# ControlBoard_p2.net
KiCad netlist of a schematic drawn in Altium Designer
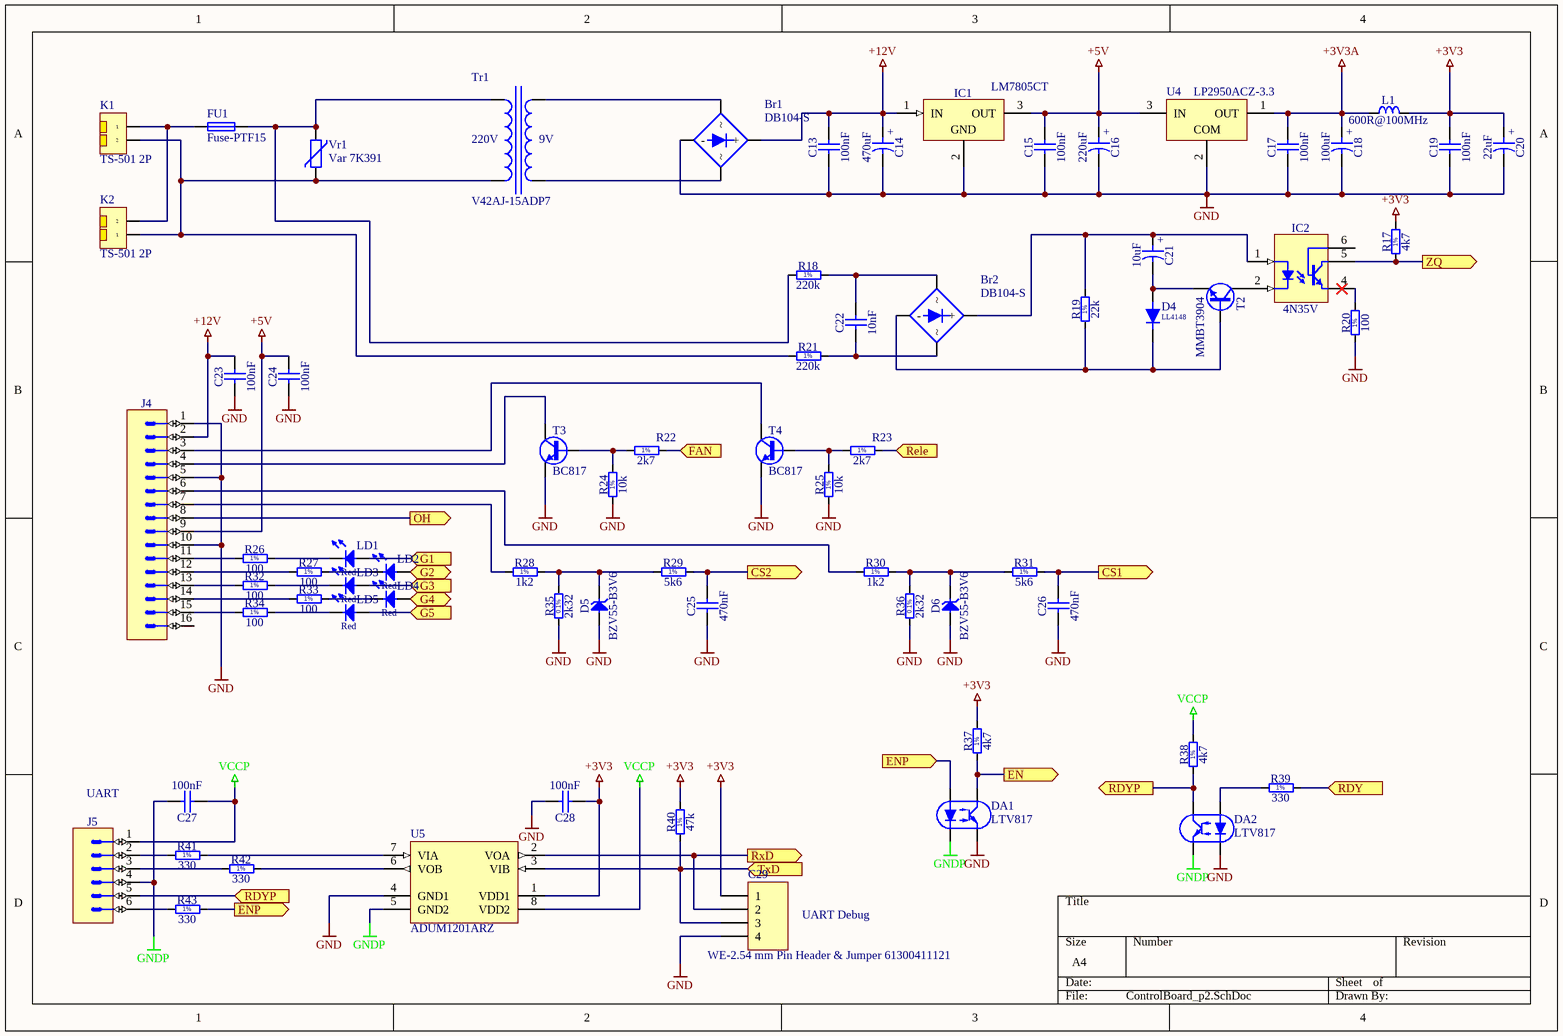
[diagram p0: ControlBoard_p2.SchDoc]

(export (version "E")
  (design (tool "Eeschema 10.0.6"))
  (components
    (comp (ref "Br1")
      (value "DB104-S")
      (footprint "DB-S")
      (description "SMD 1A 400V")
      (libsource (lib "Diodes-Bridge") (part "DB104-S"))
    )
    (comp (ref "Br2")
      (value "DB104-S")
      (footprint "DB-S")
      (description "SMD 1A 400V")
      (libsource (lib "Diodes-Bridge") (part "DB104-S"))
    )
    (comp (ref "C13")
      (value "100nF")
      (footprint "CAPC2012X135N")
      (description "Non-polarised capacitor")
      (fields
        (field (name "PART NUMBER") "CC0805_100NF_50V_10%_X7R")
        (field (name "VOLTAGE") "50V")
        (field (name "AUTHOR") "CERN DEM JLC")
      )
      (libsource (lib "Capacitors") (part "Capacitor - non polarized"))
    )
    (comp (ref "C14")
      (value "470uF")
      (footprint "CAPPR500-1050X2200")
      (description "Polarised capacitor")
      (fields
        (field (name "PART NUMBER") "CAER_470UF_25V_20%_500-1050X2200_LESR0R062")
        (field (name "VOLTAGE") "25V")
        (field (name "AUTHOR") "CERN DEM JLC")
      )
      (libsource (lib "Capacitors") (part "Capacitor - polarized"))
    )
    (comp (ref "C15")
      (value "100nF")
      (footprint "CAPC2012X135N")
      (description "Non-polarised capacitor")
      (fields
        (field (name "PART NUMBER") "CC0805_100NF_50V_10%_X7R")
        (field (name "VOLTAGE") "50V")
        (field (name "AUTHOR") "CERN DEM JLC")
      )
      (libsource (lib "Capacitors") (part "Capacitor - non polarized"))
    )
    (comp (ref "C16")
      (value "220uF")
      (footprint "CAPPR350-850X1300")
      (description "Polarised capacitor")
      (fields
        (field (name "PART NUMBER") "CAER_220UF_25V_20%_RUBYCON_25YXF220M8X11.5")
        (field (name "VOLTAGE") "25V")
        (field (name "AUTHOR") "CERN DEM JLC")
      )
      (libsource (lib "Capacitors") (part "Capacitor - polarized"))
    )
    (comp (ref "C17")
      (value "100nF")
      (footprint "CAPC2012X135N")
      (description "Non-polarised capacitor")
      (fields
        (field (name "PART NUMBER") "CC0805_100NF_50V_10%_X7R")
        (field (name "VOLTAGE") "50V")
        (field (name "AUTHOR") "CERN DEM JLC")
      )
      (libsource (lib "Capacitors") (part "Capacitor - non polarized"))
    )
    (comp (ref "C18")
      (value "100uF")
      (footprint "CAPPR350-850X800")
      (description "Polarised capacitor")
      (fields
        (field (name "PART NUMBER") "CAER_100UF_25V_20%_RUBYCON_25ML100M8X7")
        (field (name "VOLTAGE") "25V")
        (field (name "AUTHOR") "CERN DEM JMW")
      )
      (libsource (lib "Capacitors") (part "Capacitor - polarized"))
    )
    (comp (ref "C19")
      (value "100nF")
      (footprint "CAPC2012X135N")
      (description "Non-polarised capacitor")
      (fields
        (field (name "PART NUMBER") "CC0805_100NF_50V_10%_X7R")
        (field (name "VOLTAGE") "50V")
        (field (name "AUTHOR") "CERN DEM JLC")
      )
      (libsource (lib "Capacitors") (part "Capacitor - non polarized"))
    )
    (comp (ref "C20")
      (value "22uF")
      (footprint "CAPPRB254-600X990")
      (description "Polarised capacitor")
      (fields
        (field (name "PART NUMBER") "CTEB_22UF_16V_10%_254-600X990")
        (field (name "VOLTAGE") "16V")
        (field (name "AUTHOR") "CERN DEM JLC")
      )
      (libsource (lib "Capacitors") (part "Capacitor - polarized"))
    )
    (comp (ref "C21")
      (value "10uF")
      (footprint "CAPPR200-500X1100")
      (description "Polarised capacitor")
      (fields
        (field (name "PART NUMBER") "CAER_10UF_63V_20%_PANASONIC_ECA1JM100")
        (field (name "VOLTAGE") "63V")
        (field (name "AUTHOR") "CERN DEM JLC")
      )
      (libsource (lib "Capacitors") (part "Capacitor - polarized"))
    )
    (comp (ref "C22")
      (value "10nF")
      (footprint "CAPR500-300X720X650")
      (description "Non-polarised capacitor")
      (fields
        (field (name "PART NUMBER") "CPER_10NF_400V_10%_500-300X720X650")
        (field (name "VOLTAGE") "400VDC/200VAC")
        (field (name "AUTHOR") "CERN DEM JLC")
      )
      (libsource (lib "Capacitors") (part "Capacitor - non polarized"))
    )
    (comp (ref "C23")
      (value "100nF")
      (footprint "CAPC2012X135N")
      (description "Non-polarised capacitor")
      (fields
        (field (name "PART NUMBER") "CC0805_100NF_50V_10%_X7R")
        (field (name "VOLTAGE") "50V")
        (field (name "AUTHOR") "CERN DEM JLC")
      )
      (libsource (lib "Capacitors") (part "Capacitor - non polarized"))
    )
    (comp (ref "C24")
      (value "100nF")
      (footprint "CAPC2012X135N")
      (description "Non-polarised capacitor")
      (fields
        (field (name "PART NUMBER") "CC0805_100NF_50V_10%_X7R")
        (field (name "VOLTAGE") "50V")
        (field (name "AUTHOR") "CERN DEM JLC")
      )
      (libsource (lib "Capacitors") (part "Capacitor - non polarized"))
    )
    (comp (ref "C25")
      (value "470nF")
      (footprint "CAPC2012X110N")
      (description "Non-polarised capacitor")
      (fields
        (field (name "PART NUMBER") "CC0805_470NF_50V_10%_X7R")
        (field (name "VOLTAGE") "50V")
        (field (name "AUTHOR") "CERN DEM JLC")
      )
      (libsource (lib "Capacitors") (part "Capacitor - non polarized"))
    )
    (comp (ref "C26")
      (value "470nF")
      (footprint "CAPC2012X110N")
      (description "Non-polarised capacitor")
      (fields
        (field (name "PART NUMBER") "CC0805_470NF_50V_10%_X7R")
        (field (name "VOLTAGE") "50V")
        (field (name "AUTHOR") "CERN DEM JLC")
      )
      (libsource (lib "Capacitors") (part "Capacitor - non polarized"))
    )
    (comp (ref "C27")
      (value "100nF")
      (footprint "CAPC2012X135N")
      (description "Non-polarised capacitor")
      (fields
        (field (name "PART NUMBER") "CC0805_100NF_50V_10%_X7R")
        (field (name "VOLTAGE") "50V")
        (field (name "AUTHOR") "CERN DEM JLC")
      )
      (libsource (lib "Capacitors") (part "Capacitor - non polarized"))
    )
    (comp (ref "C28")
      (value "100nF")
      (footprint "CAPC2012X135N")
      (description "Non-polarised capacitor")
      (fields
        (field (name "PART NUMBER") "CC0805_100NF_50V_10%_X7R")
        (field (name "VOLTAGE") "50V")
        (field (name "AUTHOR") "CERN DEM JLC")
      )
      (libsource (lib "Capacitors") (part "Capacitor - non polarized"))
    )
    (comp (ref "C29")
      (value "WE-2.54 mm Pin Header & Jumper 61300411121")
      (footprint "61300411121")
      (description "WR-PHD 2.54mm Pin Header")
      (fields
        (field (name "MANUFACTURER") "WЁ№rth Elektronik eiSos GmbH")
        (field (name "PARTNO") "61300411121")
        (field (name "CREATED BY") "Karrer Zheng")
      )
      (libsource (lib "WE_WR-PHD_Pin Header_2.54mm_rev15c") (part "WE-2.54 mm Pin Header & Jumper 61300411121"))
    )
    (comp (ref "D4")
      (value "LL4148")
      (footprint "SOD80/MLL34")
      (description "75V 0.3A SOD80/MLL34")
      (libsource (lib "Diodes") (part "LL4148"))
    )
    (comp (ref "D5")
      (value "BZV55-B3V6")
      (footprint "DIOMELF3515N")
      (description "Zener Diode")
      (fields
        (field (name "VOLTAGE") "3V6")
        (field (name "POWER") "500mW")
        (field (name "AUTHOR") "CERN DEM JLC")
      )
      (libsource (lib "ICs And Semiconductors") (part "Diode Zener"))
    )
    (comp (ref "D6")
      (value "BZV55-B3V6")
      (footprint "DIOMELF3515N")
      (description "Zener Diode")
      (fields
        (field (name "VOLTAGE") "3V6")
        (field (name "POWER") "500mW")
        (field (name "AUTHOR") "CERN DEM JLC")
      )
      (libsource (lib "ICs And Semiconductors") (part "Diode Zener"))
    )
    (comp (ref "DA1")
      (value "LTV817")
      (footprint "DIL4-300a")
      (libsource (lib "Opto Coupler") (part "LTV817"))
    )
    (comp (ref "DA2") (value "LTV817") (footprint "DIL4-300a") (libsource (lib "") (part "LTV817_1")))
    (comp (ref "FU1")
      (value "Fuse-PTF15")
      (footprint "FUSE-MCH")
      (description "5mm 6.3A")
      (libsource (lib "Devise") (part "Fuse-PTF15"))
    )
    (comp (ref "IC1")
      (value "LM7805CT")
      (footprint "TO-220-V")
      (description "3-Terminal Regulator 1=IN 2=GND 3=OUT")
      (fields
        (field (name "PART NUMBER") "LM7805CT_v")
        (field (name "MANUFACTURER") "FAIRCHILD SEMICONDUCTOR")
        (field (name "AUTHOR") "CERN DEM JLC")
      )
      (libsource (lib "ICs And Semiconductors") (part "REG3 1IN-2GND-3OUT"))
    )
    (comp (ref "IC2")
      (value "4N35V")
      (footprint "DIP6-300")
      (description "Single Optocoupler with Base")
      (fields
        (field (name "MANUFACTURER") "VISHAY SEMICONDUCTORS")
        (field (name "MANUFACTURER PART NUMBER") "4N25V")
        (field (name "AUTHOR") "CERN DEM JLC")
      )
      (libsource (lib "ICs And Semiconductors") (part "Optocoupler Type4"))
    )
    (comp (ref "J4")
      (value "Header 16")
      (footprint "3M_N2516-6002RB")
      (description "Connector 16 Male")
      (fields
        (field (name "PART NUMBER") "3M_N2516-6002RB")
        (field (name "MANUFACTURER") "3M")
        (field (name "AUTHOR") "CERN DEM JLC")
      )
      (libsource (lib "Connectors") (part "Connector 16 Male"))
    )
    (comp (ref "J5")
      (value "KK®")
      (footprint "MOLEX_22-27-2061")
      (description "Connector 6 Male")
      (fields
        (field (name "PART NUMBER") "MOLEX_22-27-2061")
        (field (name "MANUFACTURER") "MOLEX")
        (field (name "AUTHOR") "CERN DEM JMW")
      )
      (libsource (lib "Connectors") (part "Connector 6 Male"))
    )
    (comp (ref "K1")
      (value "TS-501 2P")
      (footprint "TS-501 2P-2.5")
      (description "10A/300V AC 5mm")
      (libsource (lib "Connektor") (part "TS-501 2P"))
    )
    (comp (ref "K2")
      (value "TS-501 2P")
      (footprint "TS-501 2P-2.5")
      (description "10A/300V AC 5mm")
      (libsource (lib "") (part "TS-501 2P_1"))
    )
    (comp (ref "L1")
      (value "600R@100MHz")
      (footprint "INDC2012X110N")
      (description "Inductor")
      (fields
        (field (name "PART NUMBER") "IND0805_WURTH_742792040")
        (field (name "POWER") "2A")
        (field (name "AUTHOR") "CERN DEM JLC")
      )
      (libsource (lib "Inductors & Transformers") (part "Inductor"))
    )
    (comp (ref "LD1")
      (value "Super Red")
      (footprint "LED_OSRAM_LSR976")
      (description "LED Red 1C 2A")
      (fields
        (field (name "PART NUMBER") "LED_OSRAM_LSR976")
        (field (name "MANUFACTURER") "OSRAM")
        (field (name "AUTHOR") "CERN DEM JLC")
      )
      (libsource (lib "ICs And Semiconductors") (part "LED Red 1C 2A"))
    )
    (comp (ref "LD2")
      (value "Super Red")
      (footprint "LED_OSRAM_LSR976")
      (description "LED Red 1C 2A")
      (fields
        (field (name "PART NUMBER") "LED_OSRAM_LSR976")
        (field (name "MANUFACTURER") "OSRAM")
        (field (name "AUTHOR") "CERN DEM JLC")
      )
      (libsource (lib "ICs And Semiconductors") (part "LED Red 1C 2A"))
    )
    (comp (ref "LD3")
      (value "Super Red")
      (footprint "LED_OSRAM_LSR976")
      (description "LED Red 1C 2A")
      (fields
        (field (name "PART NUMBER") "LED_OSRAM_LSR976")
        (field (name "MANUFACTURER") "OSRAM")
        (field (name "AUTHOR") "CERN DEM JLC")
      )
      (libsource (lib "ICs And Semiconductors") (part "LED Red 1C 2A"))
    )
    (comp (ref "LD4")
      (value "Super Red")
      (footprint "LED_OSRAM_LSR976")
      (description "LED Red 1C 2A")
      (fields
        (field (name "PART NUMBER") "LED_OSRAM_LSR976")
        (field (name "MANUFACTURER") "OSRAM")
        (field (name "AUTHOR") "CERN DEM JLC")
      )
      (libsource (lib "ICs And Semiconductors") (part "LED Red 1C 2A"))
    )
    (comp (ref "LD5")
      (value "Super Red")
      (footprint "LED_OSRAM_LSR976")
      (description "LED Red 1C 2A")
      (fields
        (field (name "PART NUMBER") "LED_OSRAM_LSR976")
        (field (name "MANUFACTURER") "OSRAM")
        (field (name "AUTHOR") "CERN DEM JLC")
      )
      (libsource (lib "ICs And Semiconductors") (part "LED Red 1C 2A"))
    )
    (comp (ref "R17")
      (value "4k7")
      (footprint "RESC2012X60N")
      (description "Resistor - 1%")
      (fields
        (field (name "PART NUMBER") "R0805_4K7_1%_0.125W_100PPM")
        (field (name "POWER") "0.125W")
        (field (name "AUTHOR") "CERN DEM JLC")
      )
      (libsource (lib "Resistors") (part "Resistor - 1%"))
    )
    (comp (ref "R18")
      (value "220k")
      (footprint "RES1016-630X250")
      (description "Resistor - 1%")
      (fields
        (field (name "PART NUMBER") "RMF_220K_1%_0.6W_50PPM_1016-630X250")
        (field (name "POWER") "0.6W")
        (field (name "AUTHOR") "CERN DEM JLC")
      )
      (libsource (lib "Resistors") (part "Resistor - 1%"))
    )
    (comp (ref "R19")
      (value "22k")
      (footprint "RESC2012X60N")
      (description "Resistor - 1%")
      (fields
        (field (name "PART NUMBER") "R0805_22K_1%_0.125W_100PPM")
        (field (name "POWER") "0.125W")
        (field (name "AUTHOR") "CERN DEM JLC")
      )
      (libsource (lib "Resistors") (part "Resistor - 1%"))
    )
    (comp (ref "R20")
      (value "100")
      (footprint "RESC2012X60N")
      (description "Resistor - 1%")
      (fields
        (field (name "PART NUMBER") "R0805_100R_1%_0.125W_100PPM")
        (field (name "POWER") "0.125W")
        (field (name "AUTHOR") "CERN DEM JLC")
      )
      (libsource (lib "Resistors") (part "Resistor - 1%"))
    )
    (comp (ref "R21")
      (value "220k")
      (footprint "RES1016-630X250")
      (description "Resistor - 1%")
      (fields
        (field (name "PART NUMBER") "RMF_220K_1%_0.6W_50PPM_1016-630X250")
        (field (name "POWER") "0.6W")
        (field (name "AUTHOR") "CERN DEM JLC")
      )
      (libsource (lib "Resistors") (part "Resistor - 1%"))
    )
    (comp (ref "R22")
      (value "2k7")
      (footprint "RESC2012X60N")
      (description "Resistor - 1%")
      (fields
        (field (name "PART NUMBER") "R0805_2K7_1%_0.125W_100PPM")
        (field (name "POWER") "0.125W")
        (field (name "AUTHOR") "CERN DEM JLC")
      )
      (libsource (lib "Resistors") (part "Resistor - 1%"))
    )
    (comp (ref "R23")
      (value "2k7")
      (footprint "RESC2012X60N")
      (description "Resistor - 1%")
      (fields
        (field (name "PART NUMBER") "R0805_2K7_1%_0.125W_100PPM")
        (field (name "POWER") "0.125W")
        (field (name "AUTHOR") "CERN DEM JLC")
      )
      (libsource (lib "Resistors") (part "Resistor - 1%"))
    )
    (comp (ref "R24")
      (value "10k")
      (footprint "RESC2012X60N")
      (description "Resistor - 1%")
      (fields
        (field (name "PART NUMBER") "R0805_10K_1%_0.125W_100PPM")
        (field (name "POWER") "0.125W")
        (field (name "AUTHOR") "CERN DEM JLC")
      )
      (libsource (lib "Resistors") (part "Resistor - 1%"))
    )
    (comp (ref "R25")
      (value "10k")
      (footprint "RESC2012X60N")
      (description "Resistor - 1%")
      (fields
        (field (name "PART NUMBER") "R0805_10K_1%_0.125W_100PPM")
        (field (name "POWER") "0.125W")
        (field (name "AUTHOR") "CERN DEM JLC")
      )
      (libsource (lib "Resistors") (part "Resistor - 1%"))
    )
    (comp (ref "R26")
      (value "100")
      (footprint "RESC2012X60N")
      (description "Resistor - 1%")
      (fields
        (field (name "PART NUMBER") "R0805_100R_1%_0.125W_100PPM")
        (field (name "POWER") "0.125W")
        (field (name "AUTHOR") "CERN DEM JLC")
      )
      (libsource (lib "Resistors") (part "Resistor - 1%"))
    )
    (comp (ref "R27")
      (value "100")
      (footprint "RESC2012X60N")
      (description "Resistor - 1%")
      (fields
        (field (name "PART NUMBER") "R0805_100R_1%_0.125W_100PPM")
        (field (name "POWER") "0.125W")
        (field (name "AUTHOR") "CERN DEM JLC")
      )
      (libsource (lib "Resistors") (part "Resistor - 1%"))
    )
    (comp (ref "R28")
      (value "1k2")
      (footprint "RESC2012X60N")
      (description "Resistor - 1%")
      (fields
        (field (name "PART NUMBER") "R0805_1K2_1%_0.125W_100PPM")
        (field (name "POWER") "0.125W")
        (field (name "AUTHOR") "CERN DEM JLC")
      )
      (libsource (lib "Resistors") (part "Resistor - 1%"))
    )
    (comp (ref "R29")
      (value "5k6")
      (footprint "RESC2012X60N")
      (description "Resistor - 1%")
      (fields
        (field (name "PART NUMBER") "R0805_5K6_1%_0.125W_100PPM")
        (field (name "POWER") "0.125W")
        (field (name "AUTHOR") "CERN DEM JLC")
      )
      (libsource (lib "Resistors") (part "Resistor - 1%"))
    )
    (comp (ref "R30")
      (value "1k2")
      (footprint "RESC2012X60N")
      (description "Resistor - 1%")
      (fields
        (field (name "PART NUMBER") "R0805_1K2_1%_0.125W_100PPM")
        (field (name "POWER") "0.125W")
        (field (name "AUTHOR") "CERN DEM JLC")
      )
      (libsource (lib "Resistors") (part "Resistor - 1%"))
    )
    (comp (ref "R31")
      (value "5k6")
      (footprint "RESC2012X60N")
      (description "Resistor - 1%")
      (fields
        (field (name "PART NUMBER") "R0805_5K6_1%_0.125W_100PPM")
        (field (name "POWER") "0.125W")
        (field (name "AUTHOR") "CERN DEM JLC")
      )
      (libsource (lib "Resistors") (part "Resistor - 1%"))
    )
    (comp (ref "R32")
      (value "100")
      (footprint "RESC2012X60N")
      (description "Resistor - 1%")
      (fields
        (field (name "PART NUMBER") "R0805_100R_1%_0.125W_100PPM")
        (field (name "POWER") "0.125W")
        (field (name "AUTHOR") "CERN DEM JLC")
      )
      (libsource (lib "Resistors") (part "Resistor - 1%"))
    )
    (comp (ref "R33")
      (value "100")
      (footprint "RESC2012X60N")
      (description "Resistor - 1%")
      (fields
        (field (name "PART NUMBER") "R0805_100R_1%_0.125W_100PPM")
        (field (name "POWER") "0.125W")
        (field (name "AUTHOR") "CERN DEM JLC")
      )
      (libsource (lib "Resistors") (part "Resistor - 1%"))
    )
    (comp (ref "R34")
      (value "100")
      (footprint "RESC2012X60N")
      (description "Resistor - 1%")
      (fields
        (field (name "PART NUMBER") "R0805_100R_1%_0.125W_100PPM")
        (field (name "POWER") "0.125W")
        (field (name "AUTHOR") "CERN DEM JLC")
      )
      (libsource (lib "Resistors") (part "Resistor - 1%"))
    )
    (comp (ref "R35")
      (value "2k32")
      (footprint "RESC2012X60N")
      (description "Resistor - 0.1%")
      (fields
        (field (name "PART NUMBER") "R0805_2K32_0.1%_0.1W_10PPM")
        (field (name "POWER") "0.1W")
        (field (name "AUTHOR") "CERN DEM JLC")
      )
      (libsource (lib "Resistors") (part "Resistor - 0.1%"))
    )
    (comp (ref "R36")
      (value "2k32")
      (footprint "RESC2012X60N")
      (description "Resistor - 0.1%")
      (fields
        (field (name "PART NUMBER") "R0805_2K32_0.1%_0.1W_10PPM")
        (field (name "POWER") "0.1W")
        (field (name "AUTHOR") "CERN DEM JLC")
      )
      (libsource (lib "Resistors") (part "Resistor - 0.1%"))
    )
    (comp (ref "R37")
      (value "4k7")
      (footprint "RESC2012X60N")
      (description "Resistor - 1%")
      (fields
        (field (name "PART NUMBER") "R0805_4K7_1%_0.125W_100PPM")
        (field (name "POWER") "0.125W")
        (field (name "AUTHOR") "CERN DEM JLC")
      )
      (libsource (lib "Resistors") (part "Resistor - 1%"))
    )
    (comp (ref "R38")
      (value "4k7")
      (footprint "RESC2012X60N")
      (description "Resistor - 1%")
      (fields
        (field (name "PART NUMBER") "R0805_4K7_1%_0.125W_100PPM")
        (field (name "POWER") "0.125W")
        (field (name "AUTHOR") "CERN DEM JLC")
      )
      (libsource (lib "Resistors") (part "Resistor - 1%"))
    )
    (comp (ref "R39")
      (value "330")
      (footprint "RESC2012X60N")
      (description "Resistor - 1%")
      (fields
        (field (name "PART NUMBER") "R0805_330R_1%_0.125W_100PPM")
        (field (name "POWER") "0.125W")
        (field (name "AUTHOR") "CERN DEM JLC")
      )
      (libsource (lib "Resistors") (part "Resistor - 1%"))
    )
    (comp (ref "R40")
      (value "47k")
      (footprint "RESC2012X60N")
      (description "Resistor - 1%")
      (fields
        (field (name "PART NUMBER") "R0805_47K_1%_0.125W_100PPM")
        (field (name "POWER") "0.125W")
        (field (name "AUTHOR") "CERN DEM JLC")
      )
      (libsource (lib "Resistors") (part "Resistor - 1%"))
    )
    (comp (ref "R41")
      (value "330")
      (footprint "RESC2012X60N")
      (description "Resistor - 1%")
      (fields
        (field (name "PART NUMBER") "R0805_330R_1%_0.125W_100PPM")
        (field (name "POWER") "0.125W")
        (field (name "AUTHOR") "CERN DEM JLC")
      )
      (libsource (lib "Resistors") (part "Resistor - 1%"))
    )
    (comp (ref "R42")
      (value "330")
      (footprint "RESC2012X60N")
      (description "Resistor - 1%")
      (fields
        (field (name "PART NUMBER") "R0805_330R_1%_0.125W_100PPM")
        (field (name "POWER") "0.125W")
        (field (name "AUTHOR") "CERN DEM JLC")
      )
      (libsource (lib "Resistors") (part "Resistor - 1%"))
    )
    (comp (ref "R43")
      (value "330")
      (footprint "RESC2012X60N")
      (description "Resistor - 1%")
      (fields
        (field (name "PART NUMBER") "R0805_330R_1%_0.125W_100PPM")
        (field (name "POWER") "0.125W")
        (field (name "AUTHOR") "CERN DEM JLC")
      )
      (libsource (lib "Resistors") (part "Resistor - 1%"))
    )
    (comp (ref "T2")
      (value "MMBT3904")
      (footprint "SOT95P230X110-3N")
      (description "NPN Transistor")
      (fields (field (name "MANUFACTURER") "NXP SEMICONDUCTORS") (field (name "AUTHOR") "CERN DEM JLC"))
      (libsource (lib "ICs And Semiconductors") (part "NPN B1 E2 C3"))
    )
    (comp (ref "T3")
      (value "BC817")
      (footprint "SOT95P230X110-3N")
      (description "NPN Transistor")
      (fields (field (name "MANUFACTURER") "NXP SEMICONDUCTORS") (field (name "AUTHOR") "CERN DEM JLC"))
      (libsource (lib "ICs And Semiconductors") (part "NPN B1 E2 C3"))
    )
    (comp (ref "T4")
      (value "BC817")
      (footprint "SOT95P230X110-3N")
      (description "NPN Transistor")
      (fields (field (name "MANUFACTURER") "NXP SEMICONDUCTORS") (field (name "AUTHOR") "CERN DEM JLC"))
      (libsource (lib "ICs And Semiconductors") (part "NPN B1 E2 C3"))
    )
    (comp (ref "Tr1")
      (value "V42AJ-15ADP7")
      (footprint "TR220-6W")
      (libsource (lib "PowerLib") (part "V42AJ-15ADP7"))
    )
    (comp (ref "U4")
      (value "LP2950ACZ-3.3")
      (footprint "LP3")
      (fields (field (name "MANUFACTURER") "Texas Instruments") (field (name "PARTNUMBER") "UA78L02ACLP"))
      (libsource (lib "TI Power Management Standard Voltage Regulator") (part "UA78L02ACLP"))
    )
    (comp (ref "U5")
      (value "ADUM1201ARZ")
      (footprint "ADI-R-8_N")
      (fields (field (name "MANUFACTURER") "Analog Devices"))
      (libsource (lib "Analog Devices Interface and Isolation Digital Isolators") (part "ADUM1201ARZ"))
    )
    (comp (ref "Vr1")
      (value "Var 7K391")
      (footprint "VAR-7K-200")
      (description "Варистор 7mm")
      (libsource (lib "Devise") (part "Var 7K391"))
    )
  )
  (nets
    (net (code "1") (name "+3V3") (class "Default")
      (node (ref "C19") (pin "2") (pinfunction "2_2") (pintype "passive"))
      (node (ref "C20") (pin "1") (pinfunction "1_1") (pintype "passive"))
      (node (ref "C28") (pin "1") (pinfunction "1_1") (pintype "passive"))
      (node (ref "C29") (pin "1") (pinfunction "1_1") (pintype "passive"))
      (node (ref "L1") (pin "2") (pinfunction "2_2") (pintype "passive"))
      (node (ref "R17") (pin "2") (pinfunction "2_2") (pintype "passive"))
      (node (ref "R37") (pin "2") (pinfunction "2_2") (pintype "passive"))
      (node (ref "R40") (pin "2") (pinfunction "2_2") (pintype "passive"))
      (node (ref "U5") (pin "1") (pinfunction "VDD1_1") (pintype "power_in"))
    )
    (net (code "2") (name "+3V3A") (class "Default")
      (node (ref "C17") (pin "2") (pinfunction "2_2") (pintype "passive"))
      (node (ref "C18") (pin "1") (pinfunction "1_1") (pintype "passive"))
      (node (ref "L1") (pin "1") (pinfunction "1_1") (pintype "passive"))
      (node (ref "U4") (pin "1") (pinfunction "OUT_1") (pintype "power_in"))
    )
    (net (code "3") (name "+5V") (class "Default")
      (node (ref "C15") (pin "2") (pinfunction "2_2") (pintype "passive"))
      (node (ref "C16") (pin "1") (pinfunction "1_1") (pintype "passive"))
      (node (ref "C24") (pin "2") (pinfunction "2_2") (pintype "passive"))
      (node (ref "IC1") (pin "3") (pinfunction "OUT_3") (pintype "power_in"))
      (node (ref "J4") (pin "9") (pinfunction "9_9") (pintype "bidirectional"))
      (node (ref "U4") (pin "3") (pinfunction "IN_3") (pintype "power_in"))
    )
    (net (code "4") (name "+12V") (class "Default")
      (node (ref "Br1") (pin "1") (pinfunction "+_1") (pintype "passive"))
      (node (ref "C13") (pin "2") (pinfunction "2_2") (pintype "passive"))
      (node (ref "C14") (pin "1") (pinfunction "1_1") (pintype "passive"))
      (node (ref "C23") (pin "2") (pinfunction "2_2") (pintype "passive"))
      (node (ref "IC1") (pin "1") (pinfunction "IN_1") (pintype "input"))
      (node (ref "J4") (pin "2") (pinfunction "2_2") (pintype "bidirectional"))
    )
    (net (code "5") (name "/CS1") (class "Default")
      (node (ref "C26") (pin "2") (pinfunction "2_2") (pintype "passive"))
      (node (ref "R31") (pin "2") (pinfunction "2_2") (pintype "passive"))
    )
    (net (code "6") (name "/CS2") (class "Default")
      (node (ref "C25") (pin "2") (pinfunction "2_2") (pintype "passive"))
      (node (ref "R29") (pin "2") (pinfunction "2_2") (pintype "passive"))
    )
    (net (code "7") (name "/EN") (class "Default")
      (node (ref "DA1") (pin "4") (pinfunction "C_4") (pintype "passive"))
      (node (ref "R37") (pin "1") (pinfunction "1_1") (pintype "passive"))
    )
    (net (code "8") (name "/ENP") (class "Default")
      (node (ref "DA1") (pin "1") (pinfunction "A_1") (pintype "passive"))
      (node (ref "R43") (pin "2") (pinfunction "2_2") (pintype "passive"))
    )
    (net (code "9") (name "/FAN") (class "Default")
      (node (ref "R22") (pin "2") (pinfunction "2_2") (pintype "passive"))
    )
    (net (code "10") (name "/G1") (class "Default")
      (node (ref "LD1") (pin "2") (pinfunction "A_2") (pintype "passive"))
    )
    (net (code "11") (name "/G2") (class "Default")
      (node (ref "LD2") (pin "2") (pinfunction "A_2") (pintype "passive"))
    )
    (net (code "12") (name "/G3") (class "Default")
      (node (ref "LD3") (pin "2") (pinfunction "A_2") (pintype "passive"))
    )
    (net (code "13") (name "/G4") (class "Default")
      (node (ref "LD4") (pin "2") (pinfunction "A_2") (pintype "passive"))
    )
    (net (code "14") (name "/G5") (class "Default")
      (node (ref "LD5") (pin "2") (pinfunction "A_2") (pintype "passive"))
    )
    (net (code "15") (name "/OH") (class "Default")
      (node (ref "J4") (pin "8") (pinfunction "8_8") (pintype "bidirectional"))
    )
    (net (code "16") (name "/RDY") (class "Default")
      (node (ref "R39") (pin "2") (pinfunction "2_2") (pintype "passive"))
    )
    (net (code "17") (name "/RDYP") (class "Default")
      (node (ref "DA2") (pin "4") (pinfunction "C_4") (pintype "passive"))
      (node (ref "J5") (pin "5") (pinfunction "5_5") (pintype "bidirectional"))
      (node (ref "R38") (pin "1") (pinfunction "1_1") (pintype "passive"))
    )
    (net (code "18") (name "/Rele") (class "Default")
      (node (ref "R23") (pin "2") (pinfunction "2_2") (pintype "passive"))
    )
    (net (code "19") (name "/RxD") (class "Default")
      (node (ref "C29") (pin "2") (pinfunction "2_2") (pintype "passive"))
      (node (ref "U5") (pin "2") (pinfunction "VOA_2") (pintype "output"))
    )
    (net (code "20") (name "/TxD") (class "Default")
      (node (ref "C29") (pin "3") (pinfunction "3_3") (pintype "passive"))
      (node (ref "R40") (pin "1") (pinfunction "1_1") (pintype "passive"))
      (node (ref "U5") (pin "3") (pinfunction "VIB_3") (pintype "input"))
    )
    (net (code "21") (name "/ZQ") (class "Default")
      (node (ref "IC2") (pin "5") (pinfunction "C_5") (pintype "open_collector"))
      (node (ref "R17") (pin "1") (pinfunction "1_1") (pintype "passive"))
    )
    (net (code "22") (name "GND") (class "Default")
      (node (ref "Br1") (pin "2") (pinfunction "-_2") (pintype "passive"))
      (node (ref "C13") (pin "1") (pinfunction "1_1") (pintype "passive"))
      (node (ref "C14") (pin "2") (pinfunction "2_2") (pintype "passive"))
      (node (ref "C15") (pin "1") (pinfunction "1_1") (pintype "passive"))
      (node (ref "C16") (pin "2") (pinfunction "2_2") (pintype "passive"))
      (node (ref "C17") (pin "1") (pinfunction "1_1") (pintype "passive"))
      (node (ref "C18") (pin "2") (pinfunction "2_2") (pintype "passive"))
      (node (ref "C19") (pin "1") (pinfunction "1_1") (pintype "passive"))
      (node (ref "C20") (pin "2") (pinfunction "2_2") (pintype "passive"))
      (node (ref "C23") (pin "1") (pinfunction "1_1") (pintype "passive"))
      (node (ref "C24") (pin "1") (pinfunction "1_1") (pintype "passive"))
      (node (ref "C25") (pin "1") (pinfunction "1_1") (pintype "passive"))
      (node (ref "C26") (pin "1") (pinfunction "1_1") (pintype "passive"))
      (node (ref "C28") (pin "2") (pinfunction "2_2") (pintype "passive"))
      (node (ref "C29") (pin "4") (pinfunction "4_4") (pintype "passive"))
      (node (ref "D5") (pin "2") (pinfunction "A_2") (pintype "passive"))
      (node (ref "D6") (pin "2") (pinfunction "A_2") (pintype "passive"))
      (node (ref "DA1") (pin "3") (pinfunction "E_3") (pintype "passive"))
      (node (ref "DA2") (pin "2") (pinfunction "C_2") (pintype "passive"))
      (node (ref "IC1") (pin "2") (pinfunction "GND_2") (pintype "power_in"))
      (node (ref "J4") (pin "1") (pinfunction "1_1") (pintype "bidirectional"))
      (node (ref "J4") (pin "10") (pinfunction "10_10") (pintype "bidirectional"))
      (node (ref "J4") (pin "5") (pinfunction "5_5") (pintype "bidirectional"))
      (node (ref "R20") (pin "1") (pinfunction "1_1") (pintype "passive"))
      (node (ref "R24") (pin "1") (pinfunction "1_1") (pintype "passive"))
      (node (ref "R25") (pin "1") (pinfunction "1_1") (pintype "passive"))
      (node (ref "R35") (pin "1") (pinfunction "1_1") (pintype "passive"))
      (node (ref "R36") (pin "1") (pinfunction "1_1") (pintype "passive"))
      (node (ref "T3") (pin "2") (pinfunction "E_2") (pintype "passive"))
      (node (ref "T4") (pin "2") (pinfunction "E_2") (pintype "passive"))
      (node (ref "U4") (pin "2") (pinfunction "COM_2") (pintype "power_in"))
      (node (ref "U5") (pin "4") (pinfunction "GND1_4") (pintype "power_in"))
    )
    (net (code "23") (name "GNDP") (class "Default")
      (node (ref "C27") (pin "2") (pinfunction "2_2") (pintype "passive"))
      (node (ref "DA1") (pin "2") (pinfunction "C_2") (pintype "passive"))
      (node (ref "DA2") (pin "3") (pinfunction "E_3") (pintype "passive"))
      (node (ref "J5") (pin "4") (pinfunction "4_4") (pintype "bidirectional"))
      (node (ref "U5") (pin "5") (pinfunction "GND2_5") (pintype "power_in"))
    )
    (net (code "24") (name "Net-(Br1-~-Pad3)") (class "Default")
      (node (ref "Br1") (pin "3") (pinfunction "~_3") (pintype "passive"))
      (node (ref "Tr1") (pin "9") (pinfunction "9_9") (pintype "passive"))
    )
    (net (code "25") (name "Net-(Br1-~-Pad4)") (class "Default")
      (node (ref "Br1") (pin "4") (pinfunction "~_4") (pintype "passive"))
      (node (ref "Tr1") (pin "7") (pinfunction "7_7") (pintype "passive"))
    )
    (net (code "26") (name "Net-(Br2-+)") (class "Default")
      (node (ref "Br2") (pin "1") (pinfunction "+_1") (pintype "passive"))
      (node (ref "C21") (pin "1") (pinfunction "1_1") (pintype "passive"))
      (node (ref "IC2") (pin "1") (pinfunction "A_1") (pintype "input"))
      (node (ref "R19") (pin "2") (pinfunction "2_2") (pintype "passive"))
    )
    (net (code "27") (name "Net-(Br2--)") (class "Default")
      (node (ref "Br2") (pin "2") (pinfunction "-_2") (pintype "passive"))
      (node (ref "D4") (pin "2") (pinfunction "C_2") (pintype "passive"))
      (node (ref "R19") (pin "1") (pinfunction "1_1") (pintype "passive"))
      (node (ref "T2") (pin "1") (pinfunction "B_1") (pintype "passive"))
    )
    (net (code "28") (name "Net-(Br2-~-Pad3)") (class "Default")
      (node (ref "Br2") (pin "3") (pinfunction "~_3") (pintype "passive"))
      (node (ref "C22") (pin "2") (pinfunction "2_2") (pintype "passive"))
      (node (ref "R18") (pin "2") (pinfunction "2_2") (pintype "passive"))
    )
    (net (code "29") (name "Net-(Br2-~-Pad4)") (class "Default")
      (node (ref "Br2") (pin "4") (pinfunction "~_4") (pintype "passive"))
      (node (ref "C22") (pin "1") (pinfunction "1_1") (pintype "passive"))
      (node (ref "R21") (pin "2") (pinfunction "2_2") (pintype "passive"))
    )
    (net (code "30") (name "Net-(D4-A)") (class "Default")
      (node (ref "C21") (pin "2") (pinfunction "2_2") (pintype "passive"))
      (node (ref "D4") (pin "1") (pinfunction "A_1") (pintype "passive"))
      (node (ref "T2") (pin "2") (pinfunction "E_2") (pintype "passive"))
    )
    (net (code "31") (name "Net-(D5-C)") (class "Default")
      (node (ref "D5") (pin "1") (pinfunction "C_1") (pintype "passive"))
      (node (ref "R28") (pin "2") (pinfunction "2_2") (pintype "passive"))
      (node (ref "R29") (pin "1") (pinfunction "1_1") (pintype "passive"))
      (node (ref "R35") (pin "2") (pinfunction "2_2") (pintype "passive"))
    )
    (net (code "32") (name "Net-(D6-C)") (class "Default")
      (node (ref "D6") (pin "1") (pinfunction "C_1") (pintype "passive"))
      (node (ref "R30") (pin "2") (pinfunction "2_2") (pintype "passive"))
      (node (ref "R31") (pin "1") (pinfunction "1_1") (pintype "passive"))
      (node (ref "R36") (pin "2") (pinfunction "2_2") (pintype "passive"))
    )
    (net (code "33") (name "Net-(DA2-A)") (class "Default")
      (node (ref "DA2") (pin "1") (pinfunction "A_1") (pintype "passive"))
      (node (ref "R39") (pin "1") (pinfunction "1_1") (pintype "passive"))
    )
    (net (code "34") (name "Net-(FU1-Pad1)") (class "Default")
      (node (ref "FU1") (pin "1") (pinfunction "1_1") (pintype "passive"))
      (node (ref "R18") (pin "1") (pinfunction "1_1") (pintype "passive"))
      (node (ref "Tr1") (pin "1") (pinfunction "1_1") (pintype "passive"))
      (node (ref "Vr1") (pin "1") (pinfunction "1_1") (pintype "passive"))
    )
    (net (code "35") (name "Net-(FU1-Pad2)") (class "Default")
      (node (ref "FU1") (pin "2") (pinfunction "2_2") (pintype "passive"))
      (node (ref "K1") (pin "1") (pinfunction "1_1") (pintype "passive"))
      (node (ref "K2") (pin "2") (pinfunction "2_2") (pintype "passive"))
    )
    (net (code "36") (name "Net-(IC2-E)") (class "Default")
      (node (ref "IC2") (pin "4") (pinfunction "E_4") (pintype "open_emitter"))
      (node (ref "R20") (pin "2") (pinfunction "2_2") (pintype "passive"))
    )
    (net (code "37") (name "Net-(J4-Pad6)") (class "Default")
      (node (ref "J4") (pin "6") (pinfunction "6_6") (pintype "bidirectional"))
      (node (ref "R30") (pin "1") (pinfunction "1_1") (pintype "passive"))
    )
    (net (code "38") (name "Net-(J4-Pad7)") (class "Default")
      (node (ref "J4") (pin "7") (pinfunction "7_7") (pintype "bidirectional"))
      (node (ref "R28") (pin "1") (pinfunction "1_1") (pintype "passive"))
    )
    (net (code "39") (name "Net-(J4-Pad11)") (class "Default")
      (node (ref "J4") (pin "11") (pinfunction "11_11") (pintype "bidirectional"))
      (node (ref "R26") (pin "1") (pinfunction "1_1") (pintype "passive"))
    )
    (net (code "40") (name "Net-(J4-Pad12)") (class "Default")
      (node (ref "J4") (pin "12") (pinfunction "12_12") (pintype "bidirectional"))
      (node (ref "R27") (pin "1") (pinfunction "1_1") (pintype "passive"))
    )
    (net (code "41") (name "Net-(J4-Pad13)") (class "Default")
      (node (ref "J4") (pin "13") (pinfunction "13_13") (pintype "bidirectional"))
      (node (ref "R32") (pin "1") (pinfunction "1_1") (pintype "passive"))
    )
    (net (code "42") (name "Net-(J4-Pad14)") (class "Default")
      (node (ref "J4") (pin "14") (pinfunction "14_14") (pintype "bidirectional"))
      (node (ref "R33") (pin "1") (pinfunction "1_1") (pintype "passive"))
    )
    (net (code "43") (name "Net-(J4-Pad15)") (class "Default")
      (node (ref "J4") (pin "15") (pinfunction "15_15") (pintype "bidirectional"))
      (node (ref "R34") (pin "1") (pinfunction "1_1") (pintype "passive"))
    )
    (net (code "44") (name "Net-(J5-Pad2)") (class "Default")
      (node (ref "J5") (pin "2") (pinfunction "2_2") (pintype "bidirectional"))
      (node (ref "R41") (pin "1") (pinfunction "1_1") (pintype "passive"))
    )
    (net (code "45") (name "Net-(J5-Pad3)") (class "Default")
      (node (ref "J5") (pin "3") (pinfunction "3_3") (pintype "bidirectional"))
      (node (ref "R42") (pin "1") (pinfunction "1_1") (pintype "passive"))
    )
    (net (code "46") (name "Net-(J5-Pad6)") (class "Default")
      (node (ref "J5") (pin "6") (pinfunction "6_6") (pintype "bidirectional"))
      (node (ref "R43") (pin "1") (pinfunction "1_1") (pintype "passive"))
    )
    (net (code "47") (name "Net-(K1-Pad2)") (class "Default")
      (node (ref "K1") (pin "2") (pinfunction "2_2") (pintype "passive"))
      (node (ref "K2") (pin "1") (pinfunction "1_1") (pintype "passive"))
      (node (ref "R21") (pin "1") (pinfunction "1_1") (pintype "passive"))
      (node (ref "Tr1") (pin "5") (pinfunction "5_5") (pintype "passive"))
      (node (ref "Vr1") (pin "2") (pinfunction "2_2") (pintype "passive"))
    )
    (net (code "48") (name "Net-(LD1-C)") (class "Default")
      (node (ref "LD1") (pin "1") (pinfunction "C_1") (pintype "passive"))
      (node (ref "R26") (pin "2") (pinfunction "2_2") (pintype "passive"))
    )
    (net (code "49") (name "Net-(LD2-C)") (class "Default")
      (node (ref "LD2") (pin "1") (pinfunction "C_1") (pintype "passive"))
      (node (ref "R27") (pin "2") (pinfunction "2_2") (pintype "passive"))
    )
    (net (code "50") (name "Net-(LD3-C)") (class "Default")
      (node (ref "LD3") (pin "1") (pinfunction "C_1") (pintype "passive"))
      (node (ref "R32") (pin "2") (pinfunction "2_2") (pintype "passive"))
    )
    (net (code "51") (name "Net-(LD4-C)") (class "Default")
      (node (ref "LD4") (pin "1") (pinfunction "C_1") (pintype "passive"))
      (node (ref "R33") (pin "2") (pinfunction "2_2") (pintype "passive"))
    )
    (net (code "52") (name "Net-(LD5-C)") (class "Default")
      (node (ref "LD5") (pin "1") (pinfunction "C_1") (pintype "passive"))
      (node (ref "R34") (pin "2") (pinfunction "2_2") (pintype "passive"))
    )
    (net (code "53") (name "Net-(T2-C)") (class "Default")
      (node (ref "IC2") (pin "2") (pinfunction "C_2") (pintype "input"))
      (node (ref "T2") (pin "3") (pinfunction "C_3") (pintype "passive"))
    )
    (net (code "54") (name "Net-(T3-B)") (class "Default")
      (node (ref "R22") (pin "1") (pinfunction "1_1") (pintype "passive"))
      (node (ref "R24") (pin "2") (pinfunction "2_2") (pintype "passive"))
      (node (ref "T3") (pin "1") (pinfunction "B_1") (pintype "passive"))
    )
    (net (code "55") (name "Net-(T3-C)") (class "Default")
      (node (ref "J4") (pin "4") (pinfunction "4_4") (pintype "bidirectional"))
      (node (ref "T3") (pin "3") (pinfunction "C_3") (pintype "passive"))
    )
    (net (code "56") (name "Net-(T4-B)") (class "Default")
      (node (ref "R23") (pin "1") (pinfunction "1_1") (pintype "passive"))
      (node (ref "R25") (pin "2") (pinfunction "2_2") (pintype "passive"))
      (node (ref "T4") (pin "1") (pinfunction "B_1") (pintype "passive"))
    )
    (net (code "57") (name "Net-(T4-C)") (class "Default")
      (node (ref "J4") (pin "3") (pinfunction "3_3") (pintype "bidirectional"))
      (node (ref "T4") (pin "3") (pinfunction "C_3") (pintype "passive"))
    )
    (net (code "58") (name "Net-(U5-VIA)") (class "Default")
      (node (ref "R41") (pin "2") (pinfunction "2_2") (pintype "passive"))
      (node (ref "U5") (pin "7") (pinfunction "VIA_7") (pintype "input"))
    )
    (net (code "59") (name "Net-(U5-VOB)") (class "Default")
      (node (ref "R42") (pin "2") (pinfunction "2_2") (pintype "passive"))
      (node (ref "U5") (pin "6") (pinfunction "VOB_6") (pintype "output"))
    )
    (net (code "60") (name "VCCP") (class "Default")
      (node (ref "C27") (pin "1") (pinfunction "1_1") (pintype "passive"))
      (node (ref "J5") (pin "1") (pinfunction "1_1") (pintype "bidirectional"))
      (node (ref "R38") (pin "2") (pinfunction "2_2") (pintype "passive"))
      (node (ref "U5") (pin "8") (pinfunction "VDD2_8") (pintype "power_in"))
    )
    (net (code "61") (name "unconnected-(IC2-C-Pad6)") (class "Default")
      (node (ref "IC2") (pin "6") (pinfunction "C_6") (pintype "open_collector"))
    )
    (net (code "62") (name "unconnected-(J4-Pad16)") (class "Default")
      (node (ref "J4") (pin "16") (pinfunction "16_16") (pintype "bidirectional"))
    )
  )
)
